# Module_Current_Probe_v1.net
KiCad netlist of a schematic drawn in EAGLE
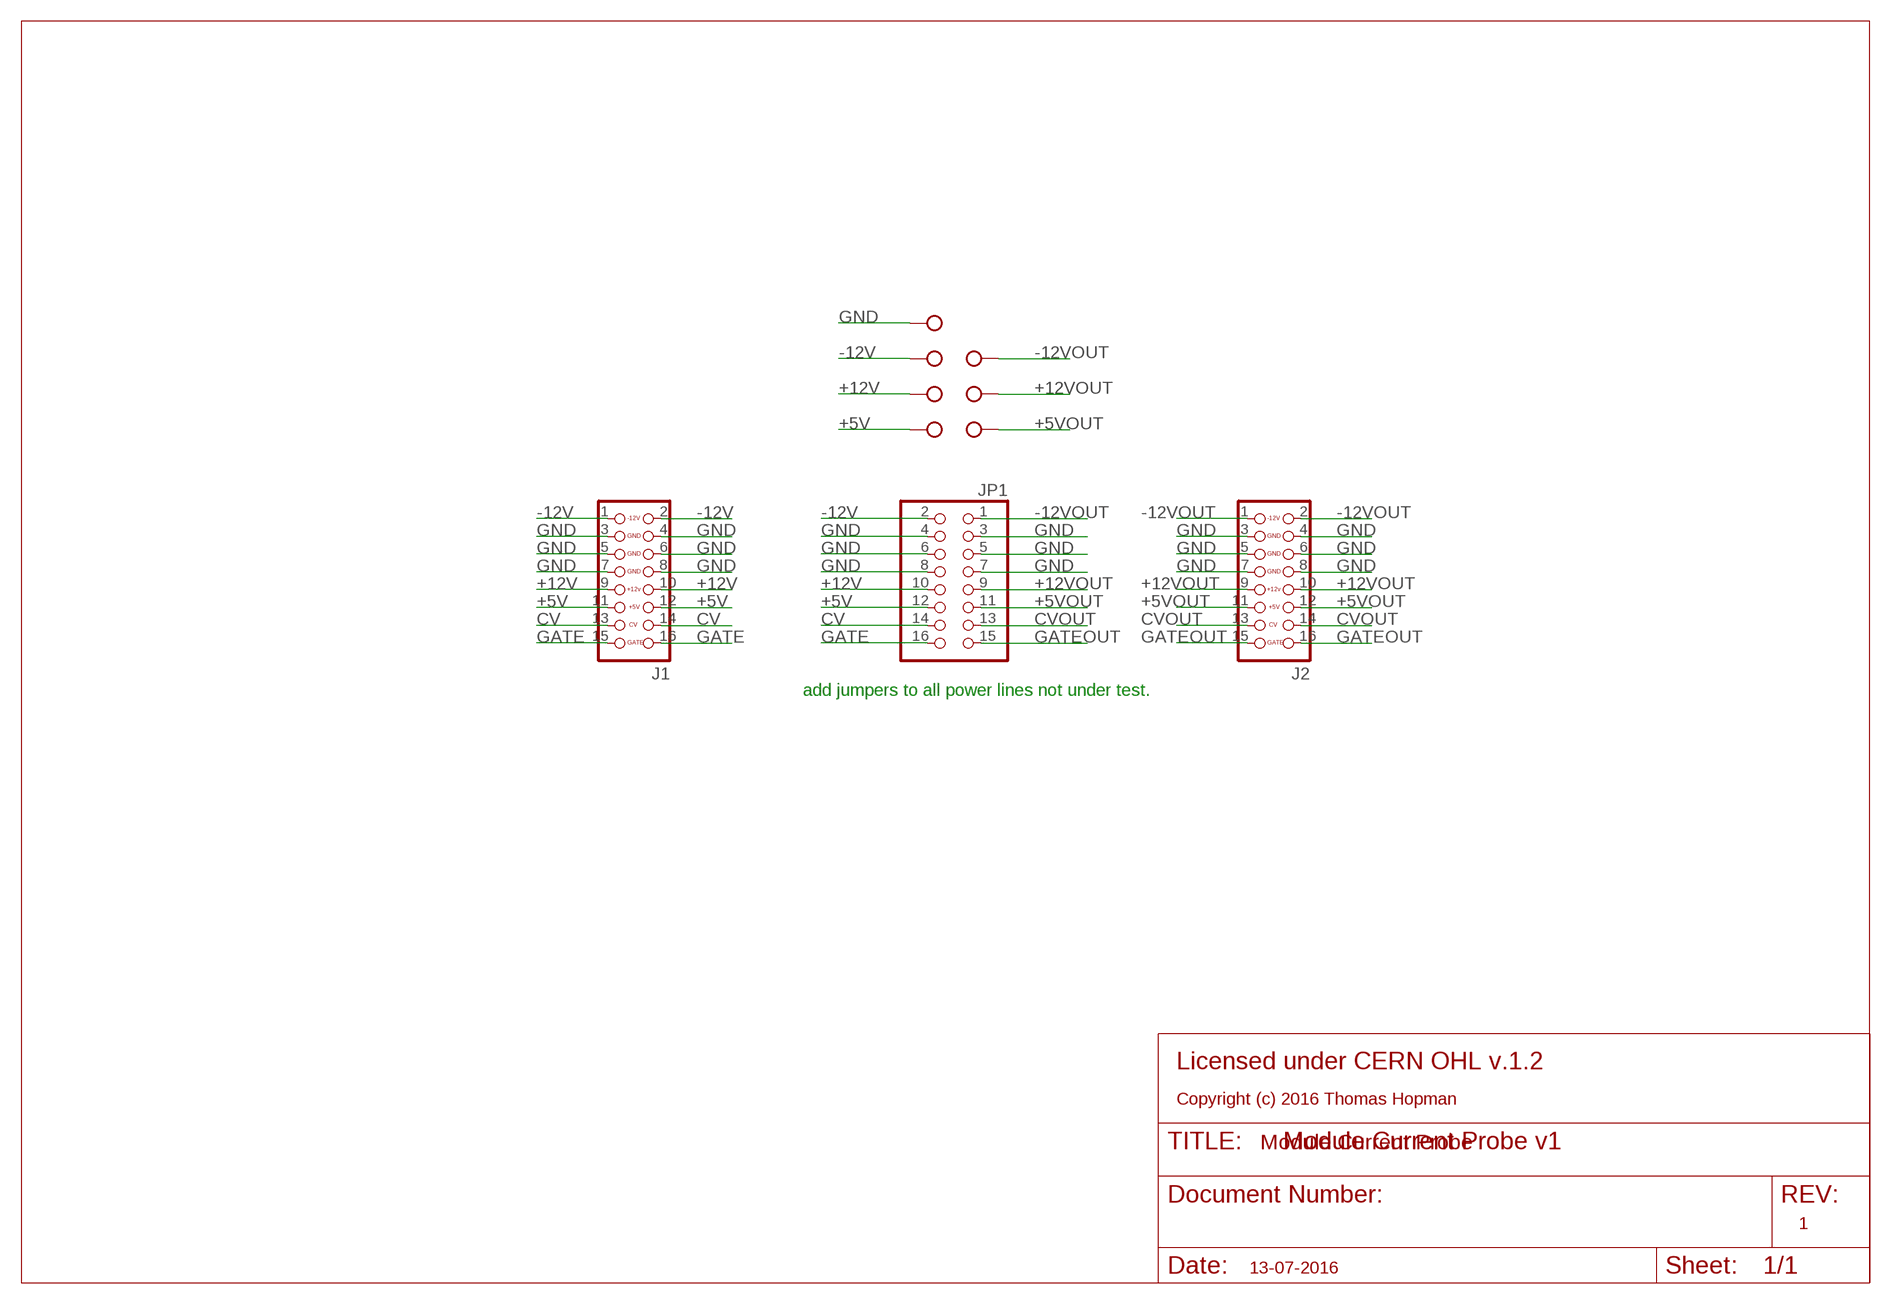
[diagram p0: schematic, sheet 1]

(export (version "E")
  (design (tool "Eeschema 10.0.6"))
  (components
    (comp (ref "J1")
      (value "CON_HEADER_2X08-PTH-SHROUDED")
      (footprint "eagle-import:PINSHRD_PTH_2X08")
      (libsource (lib "eagle-import") (part "CON_HEADER_2X08-PTH-SHROUDED"))
    )
    (comp (ref "J2")
      (value "CON_HEADER_2X08-PTH-SHROUDED")
      (footprint "eagle-import:PINSHRD_PTH_2X08")
      (libsource (lib "eagle-import") (part "CON_HEADER_2X08-PTH-SHROUDED"))
    )
    (comp (ref "J3")
      (value "BANANA-JACK")
      (footprint "eagle-import:BANANA-PRINT")
      (libsource (lib "eagle-import") (part "BANANA-JACK"))
    )
    (comp (ref "J4")
      (value "BANANA-JACK")
      (footprint "eagle-import:BANANA-PRINT")
      (libsource (lib "eagle-import") (part "BANANA-JACK"))
    )
    (comp (ref "J5")
      (value "BANANA-JACK")
      (footprint "eagle-import:BANANA-PRINT")
      (libsource (lib "eagle-import") (part "BANANA-JACK"))
    )
    (comp (ref "J6")
      (value "BANANA-JACK")
      (footprint "eagle-import:BANANA-PRINT")
      (libsource (lib "eagle-import") (part "BANANA-JACK"))
    )
    (comp (ref "J7")
      (value "BANANA-JACK")
      (footprint "eagle-import:BANANA-PRINT")
      (libsource (lib "eagle-import") (part "BANANA-JACK"))
    )
    (comp (ref "J8")
      (value "BANANA-JACK")
      (footprint "eagle-import:BANANA-PRINT")
      (libsource (lib "eagle-import") (part "BANANA-JACK"))
    )
    (comp (ref "J9")
      (value "BANANA-JACK")
      (footprint "eagle-import:BANANA-PRINT")
      (libsource (lib "eagle-import") (part "BANANA-JACK"))
    )
    (comp (ref "JP1")
      (value "PINHD-2X8")
      (footprint "eagle-import:2X08")
      (libsource (lib "eagle-import") (part "PINHD-2X8"))
    )
  )
  (nets
    (net (code "1") (name "/+5V") (class "Default")
      (node (ref "J1") (pin "11") (pinfunction "11_11") (pintype "passive"))
      (node (ref "J1") (pin "12") (pinfunction "12_12") (pintype "passive"))
      (node (ref "J5") (pin "P$1") (pinfunction "PIN_P$1") (pintype "bidirectional"))
      (node (ref "JP1") (pin "12") (pinfunction "12_12") (pintype "passive"))
    )
    (net (code "2") (name "/+5VOUT") (class "Default")
      (node (ref "J2") (pin "11") (pinfunction "11_11") (pintype "passive"))
      (node (ref "J2") (pin "12") (pinfunction "12_12") (pintype "passive"))
      (node (ref "J8") (pin "P$1") (pinfunction "PIN_P$1") (pintype "bidirectional"))
      (node (ref "JP1") (pin "11") (pinfunction "11_11") (pintype "passive"))
    )
    (net (code "3") (name "/+12V") (class "Default")
      (node (ref "J1") (pin "10") (pinfunction "10_10") (pintype "passive"))
      (node (ref "J1") (pin "9") (pinfunction "9_9") (pintype "passive"))
      (node (ref "J4") (pin "P$1") (pinfunction "PIN_P$1") (pintype "bidirectional"))
      (node (ref "JP1") (pin "10") (pinfunction "10_10") (pintype "passive"))
    )
    (net (code "4") (name "/+12VOUT") (class "Default")
      (node (ref "J2") (pin "10") (pinfunction "10_10") (pintype "passive"))
      (node (ref "J2") (pin "9") (pinfunction "9_9") (pintype "passive"))
      (node (ref "J7") (pin "P$1") (pinfunction "PIN_P$1") (pintype "bidirectional"))
      (node (ref "JP1") (pin "9") (pinfunction "9_9") (pintype "passive"))
    )
    (net (code "5") (name "/-12V") (class "Default")
      (node (ref "J1") (pin "1") (pinfunction "1_1") (pintype "passive"))
      (node (ref "J1") (pin "2") (pinfunction "2_2") (pintype "passive"))
      (node (ref "J3") (pin "P$1") (pinfunction "PIN_P$1") (pintype "bidirectional"))
      (node (ref "JP1") (pin "2") (pinfunction "2_2") (pintype "passive"))
    )
    (net (code "6") (name "/-12VOUT") (class "Default")
      (node (ref "J2") (pin "1") (pinfunction "1_1") (pintype "passive"))
      (node (ref "J2") (pin "2") (pinfunction "2_2") (pintype "passive"))
      (node (ref "J6") (pin "P$1") (pinfunction "PIN_P$1") (pintype "bidirectional"))
      (node (ref "JP1") (pin "1") (pinfunction "1_1") (pintype "passive"))
    )
    (net (code "7") (name "/CV") (class "Default")
      (node (ref "J1") (pin "13") (pinfunction "13_13") (pintype "passive"))
      (node (ref "J1") (pin "14") (pinfunction "14_14") (pintype "passive"))
      (node (ref "JP1") (pin "14") (pinfunction "14_14") (pintype "passive"))
    )
    (net (code "8") (name "/CVOUT") (class "Default")
      (node (ref "J2") (pin "13") (pinfunction "13_13") (pintype "passive"))
      (node (ref "J2") (pin "14") (pinfunction "14_14") (pintype "passive"))
      (node (ref "JP1") (pin "13") (pinfunction "13_13") (pintype "passive"))
    )
    (net (code "9") (name "/GATE") (class "Default")
      (node (ref "J1") (pin "15") (pinfunction "15_15") (pintype "passive"))
      (node (ref "J1") (pin "16") (pinfunction "16_16") (pintype "passive"))
      (node (ref "JP1") (pin "16") (pinfunction "16_16") (pintype "passive"))
    )
    (net (code "10") (name "/GATEOUT") (class "Default")
      (node (ref "J2") (pin "15") (pinfunction "15_15") (pintype "passive"))
      (node (ref "J2") (pin "16") (pinfunction "16_16") (pintype "passive"))
      (node (ref "JP1") (pin "15") (pinfunction "15_15") (pintype "passive"))
    )
    (net (code "11") (name "/GND") (class "Default")
      (node (ref "J1") (pin "3") (pinfunction "3_3") (pintype "passive"))
      (node (ref "J1") (pin "4") (pinfunction "4_4") (pintype "passive"))
      (node (ref "J1") (pin "5") (pinfunction "5_5") (pintype "passive"))
      (node (ref "J1") (pin "6") (pinfunction "6_6") (pintype "passive"))
      (node (ref "J1") (pin "7") (pinfunction "7_7") (pintype "passive"))
      (node (ref "J1") (pin "8") (pinfunction "8_8") (pintype "passive"))
      (node (ref "J2") (pin "3") (pinfunction "3_3") (pintype "passive"))
      (node (ref "J2") (pin "4") (pinfunction "4_4") (pintype "passive"))
      (node (ref "J2") (pin "5") (pinfunction "5_5") (pintype "passive"))
      (node (ref "J2") (pin "6") (pinfunction "6_6") (pintype "passive"))
      (node (ref "J2") (pin "7") (pinfunction "7_7") (pintype "passive"))
      (node (ref "J2") (pin "8") (pinfunction "8_8") (pintype "passive"))
      (node (ref "J9") (pin "P$1") (pinfunction "PIN_P$1") (pintype "bidirectional"))
      (node (ref "JP1") (pin "3") (pinfunction "3_3") (pintype "passive"))
      (node (ref "JP1") (pin "4") (pinfunction "4_4") (pintype "passive"))
      (node (ref "JP1") (pin "5") (pinfunction "5_5") (pintype "passive"))
      (node (ref "JP1") (pin "6") (pinfunction "6_6") (pintype "passive"))
      (node (ref "JP1") (pin "7") (pinfunction "7_7") (pintype "passive"))
      (node (ref "JP1") (pin "8") (pinfunction "8_8") (pintype "passive"))
    )
  )
)
